# Polsador.net
KiCad netlist of a schematic drawn in EAGLE
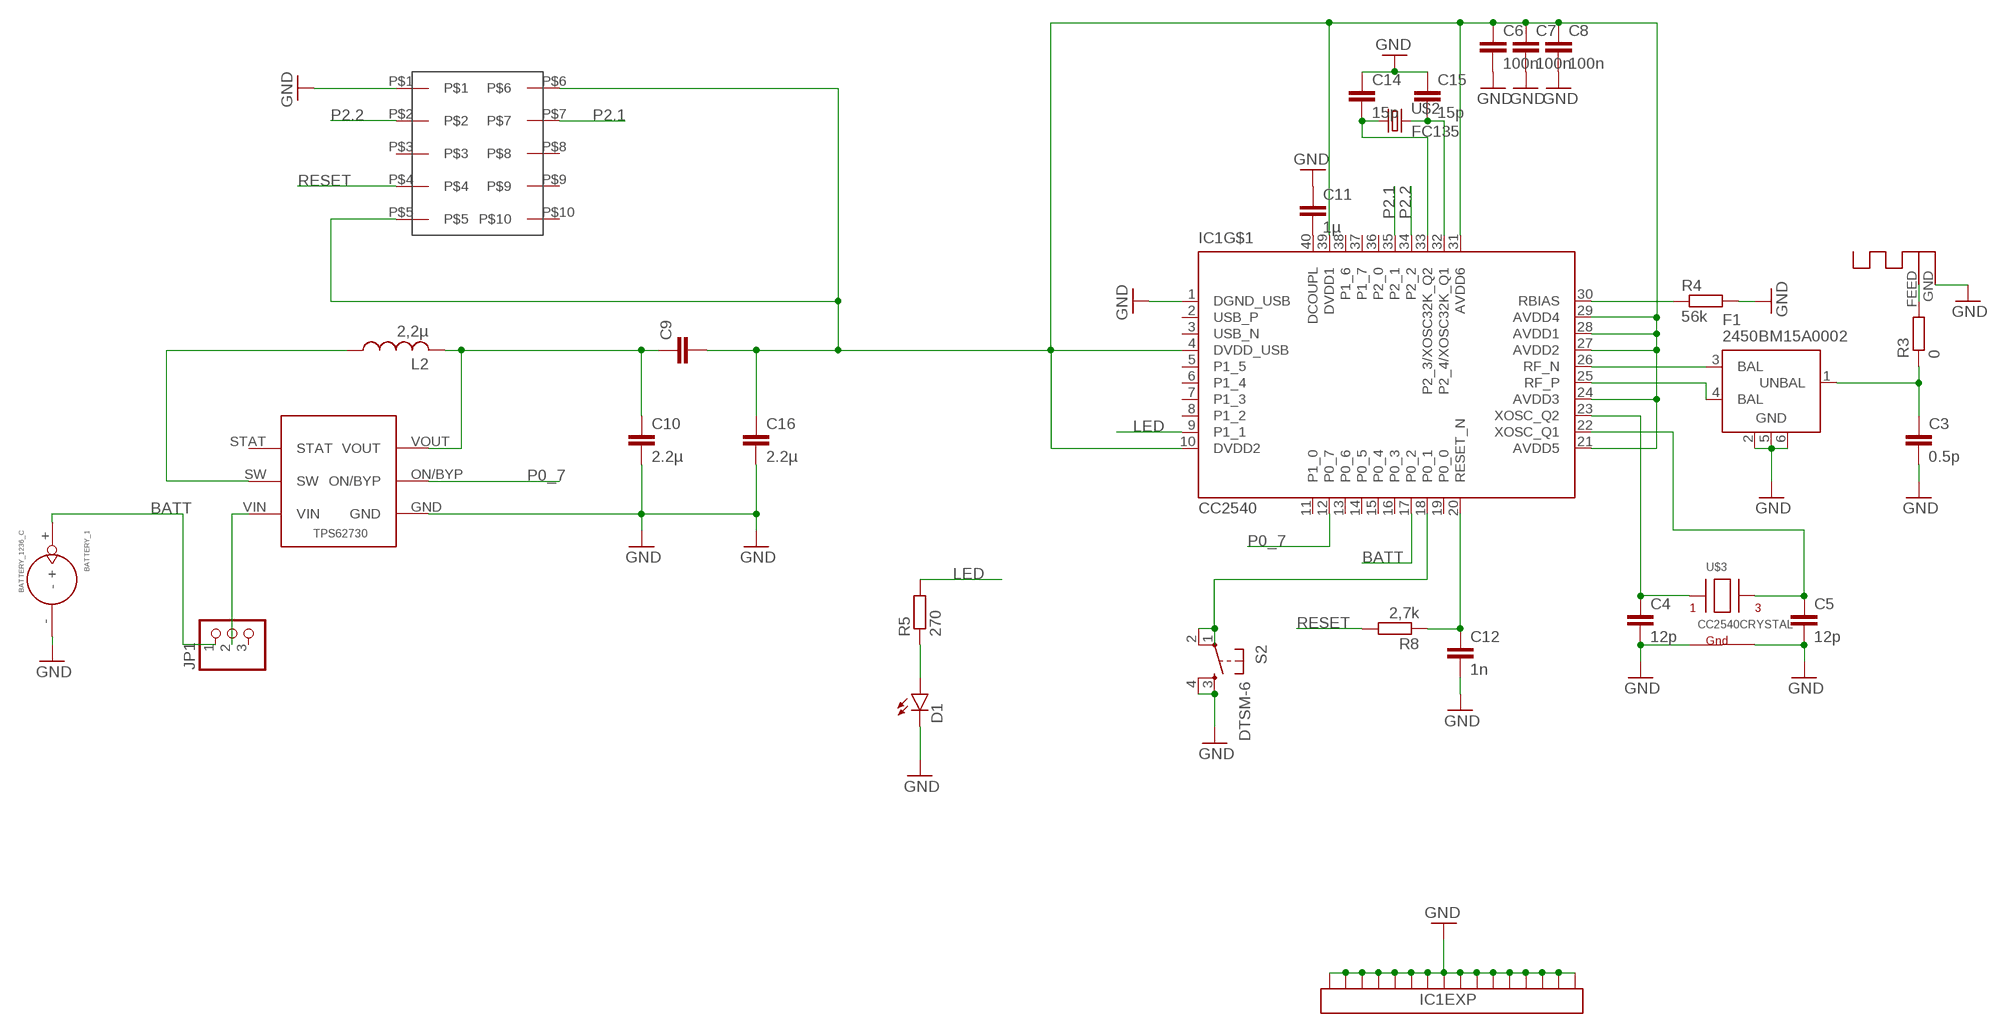
[diagram p0: schematic, sheet 1]

(export (version "E")
  (design (tool "Eeschema 10.0.6"))
  (components
    (comp (ref "ANT1")
      (value "ANTENNA")
      (footprint "eagle-import:RN-ANT")
      (libsource (lib "eagle-import") (part "ANTENNA"))
    )
    (comp (ref "BATTERY_1")
      (value "BATTERY_1236_C")
      (footprint "eagle-import:BATTERY_1236_C")
      (libsource (lib "eagle-import") (part "BATTERY_1236_C"))
    )
    (comp (ref "C3")
      (value "0.5p")
      (footprint "eagle-import:C0402K")
      (libsource (lib "eagle-import") (part "C-EUC0402K"))
    )
    (comp (ref "C4")
      (value "12p")
      (footprint "eagle-import:C0402K")
      (libsource (lib "eagle-import") (part "C-EUC0402K"))
    )
    (comp (ref "C5")
      (value "12p")
      (footprint "eagle-import:C0402K")
      (libsource (lib "eagle-import") (part "C-EUC0402K"))
    )
    (comp (ref "C6")
      (value "100n")
      (footprint "eagle-import:C0402K")
      (libsource (lib "eagle-import") (part "C-EUC0402K"))
    )
    (comp (ref "C7")
      (value "100n")
      (footprint "eagle-import:C0402K")
      (libsource (lib "eagle-import") (part "C-EUC0402K"))
    )
    (comp (ref "C8")
      (value "100n")
      (footprint "eagle-import:C0402K")
      (libsource (lib "eagle-import") (part "C-EUC0402K"))
    )
    (comp (ref "C9")
      (value "C-EUC0402")
      (footprint "eagle-import:C0402")
      (libsource (lib "eagle-import") (part "C-EUC0402"))
    )
    (comp (ref "C10")
      (value "2.2µ")
      (footprint "eagle-import:C0402K")
      (libsource (lib "eagle-import") (part "C-EUC0402K"))
    )
    (comp (ref "C11")
      (value "1µ")
      (footprint "eagle-import:C0402K")
      (libsource (lib "eagle-import") (part "C-EUC0402K"))
    )
    (comp (ref "C12")
      (value "1n")
      (footprint "eagle-import:C0402K")
      (libsource (lib "eagle-import") (part "C-EUC0402K"))
    )
    (comp (ref "C14")
      (value "15p")
      (footprint "eagle-import:C0402K")
      (libsource (lib "eagle-import") (part "C-EUC0402K"))
    )
    (comp (ref "C15")
      (value "15p")
      (footprint "eagle-import:C0402K")
      (libsource (lib "eagle-import") (part "C-EUC0402K"))
    )
    (comp (ref "C16")
      (value "2.2µ")
      (footprint "eagle-import:C0402K")
      (libsource (lib "eagle-import") (part "C-EUC0402K"))
    )
    (comp (ref "D1")
      (value "LED0603")
      (footprint "eagle-import:LED-0603")
      (libsource (lib "eagle-import") (part "LED0603"))
    )
    (comp (ref "F1")
      (value "2450BM15A0002")
      (footprint "eagle-import:2450BM15A0002")
      (libsource (lib "eagle-import") (part "2450BM15A0002"))
    )
    (comp (ref "IC1")
      (value "CC2540")
      (footprint "eagle-import:QFN40-6X6")
      (libsource (lib "eagle-import") (part "CC2540"))
    )
    (comp (ref "JP1")
      (value "PINHD-1X3")
      (footprint "eagle-import:1X03")
      (libsource (lib "eagle-import") (part "PINHD-1X3"))
    )
    (comp (ref "L2")
      (value "2,2µ")
      (footprint "eagle-import:L2012C")
      (libsource (lib "eagle-import") (part "L-USL2012C"))
    )
    (comp (ref "R3")
      (value "0")
      (footprint "eagle-import:R0402")
      (libsource (lib "eagle-import") (part "R-EU_R0402"))
    )
    (comp (ref "R4")
      (value "56k")
      (footprint "eagle-import:R0402")
      (libsource (lib "eagle-import") (part "R-EU_R0402"))
    )
    (comp (ref "R5")
      (value "270")
      (footprint "eagle-import:R0402")
      (libsource (lib "eagle-import") (part "R-EU_R0402"))
    )
    (comp (ref "R8")
      (value "2,7k")
      (footprint "eagle-import:R0402")
      (libsource (lib "eagle-import") (part "R-EU_R0402"))
    )
    (comp (ref "S2")
      (value "DTSM-6")
      (footprint "eagle-import:DTSM-6")
      (libsource (lib "eagle-import") (part "DTSM-6"))
    )
    (comp (ref "U$1")
      (value "DEBUG")
      (footprint "eagle-import:DEBUG")
      (libsource (lib "eagle-import") (part "DEBUG"))
    )
    (comp (ref "U$2")
      (value "FC135")
      (footprint "eagle-import:FC135")
      (libsource (lib "eagle-import") (part "FC135"))
    )
    (comp (ref "U$3")
      (value "CC2540CRYSTAL")
      (footprint "eagle-import:CC2540CRYSTAL")
      (libsource (lib "eagle-import") (part "CC2540CRYSTAL"))
    )
    (comp (ref "U$4")
      (value "TPS62730")
      (footprint "eagle-import:TPS62730")
      (libsource (lib "eagle-import") (part "TPS62730"))
    )
  )
  (nets
    (net (code "1") (name "/BATT") (class "Default")
      (node (ref "BATTERY_1") (pin "+") (pinfunction "+_+") (pintype "bidirectional"))
      (node (ref "IC1") (pin "17") (pinfunction "P0_2_17") (pintype "bidirectional"))
      (node (ref "JP1") (pin "1") (pinfunction "1_1") (pintype "passive"))
    )
    (net (code "2") (name "/LED") (class "Default")
      (node (ref "IC1") (pin "9") (pinfunction "P1_1_9") (pintype "bidirectional"))
      (node (ref "R5") (pin "2") (pinfunction "2_2") (pintype "passive"))
    )
    (net (code "3") (name "/P0_7") (class "Default")
      (node (ref "IC1") (pin "12") (pinfunction "P0_7_12") (pintype "bidirectional"))
      (node (ref "U$4") (pin "ON/BYP") (pinfunction "ON/BYP_ON/BYP") (pintype "bidirectional"))
    )
    (net (code "4") (name "/P2.1") (class "Default")
      (node (ref "IC1") (pin "35") (pinfunction "P2_1_35") (pintype "bidirectional"))
      (node (ref "U$1") (pin "P$7") (pinfunction "P$7_P$7") (pintype "bidirectional"))
    )
    (net (code "5") (name "/P2.2") (class "Default")
      (node (ref "IC1") (pin "34") (pinfunction "P2_2_34") (pintype "bidirectional"))
      (node (ref "U$1") (pin "P$2") (pinfunction "P$2_P$2") (pintype "bidirectional"))
    )
    (net (code "6") (name "/RESET") (class "Default")
      (node (ref "R8") (pin "2") (pinfunction "2_2") (pintype "passive"))
      (node (ref "U$1") (pin "P$4") (pinfunction "P$4_P$4") (pintype "bidirectional"))
    )
    (net (code "7") (name "GND") (class "Default")
      (node (ref "ANT1") (pin "GND") (pinfunction "GND_GND") (pintype "passive"))
      (node (ref "BATTERY_1") (pin "-") (pinfunction "-_-") (pintype "bidirectional"))
      (node (ref "C10") (pin "2") (pinfunction "2_2") (pintype "passive"))
      (node (ref "C11") (pin "1") (pinfunction "1_1") (pintype "passive"))
      (node (ref "C12") (pin "2") (pinfunction "2_2") (pintype "passive"))
      (node (ref "C14") (pin "1") (pinfunction "1_1") (pintype "passive"))
      (node (ref "C15") (pin "1") (pinfunction "1_1") (pintype "passive"))
      (node (ref "C16") (pin "2") (pinfunction "2_2") (pintype "passive"))
      (node (ref "C3") (pin "2") (pinfunction "2_2") (pintype "passive"))
      (node (ref "C4") (pin "2") (pinfunction "2_2") (pintype "passive"))
      (node (ref "C5") (pin "2") (pinfunction "2_2") (pintype "passive"))
      (node (ref "C6") (pin "2") (pinfunction "2_2") (pintype "passive"))
      (node (ref "C7") (pin "2") (pinfunction "2_2") (pintype "passive"))
      (node (ref "C8") (pin "2") (pinfunction "2_2") (pintype "passive"))
      (node (ref "D1") (pin "C") (pinfunction "C_C") (pintype "passive"))
      (node (ref "F1") (pin "2") (pinfunction "GND_2") (pintype "passive"))
      (node (ref "F1") (pin "5") (pinfunction "GND_5") (pintype "passive"))
      (node (ref "F1") (pin "6") (pinfunction "GND_6") (pintype "passive"))
      (node (ref "IC1") (pin "1") (pinfunction "DGND_USB_1") (pintype "power_in"))
      (node (ref "IC1") (pin "EXP@1") (pinfunction "EXP16_EXP@1") (pintype "input"))
      (node (ref "IC1") (pin "EXP@10") (pinfunction "EXP16_EXP@10") (pintype "input"))
      (node (ref "IC1") (pin "EXP@11") (pinfunction "EXP16_EXP@11") (pintype "input"))
      (node (ref "IC1") (pin "EXP@12") (pinfunction "EXP16_EXP@12") (pintype "input"))
      (node (ref "IC1") (pin "EXP@13") (pinfunction "EXP16_EXP@13") (pintype "input"))
      (node (ref "IC1") (pin "EXP@14") (pinfunction "EXP16_EXP@14") (pintype "input"))
      (node (ref "IC1") (pin "EXP@15") (pinfunction "EXP16_EXP@15") (pintype "input"))
      (node (ref "IC1") (pin "EXP@16") (pinfunction "EXP16_EXP@16") (pintype "input"))
      (node (ref "IC1") (pin "EXP@2") (pinfunction "EXP16_EXP@2") (pintype "input"))
      (node (ref "IC1") (pin "EXP@3") (pinfunction "EXP16_EXP@3") (pintype "input"))
      (node (ref "IC1") (pin "EXP@4") (pinfunction "EXP16_EXP@4") (pintype "input"))
      (node (ref "IC1") (pin "EXP@5") (pinfunction "EXP16_EXP@5") (pintype "input"))
      (node (ref "IC1") (pin "EXP@6") (pinfunction "EXP16_EXP@6") (pintype "input"))
      (node (ref "IC1") (pin "EXP@7") (pinfunction "EXP16_EXP@7") (pintype "input"))
      (node (ref "IC1") (pin "EXP@8") (pinfunction "EXP16_EXP@8") (pintype "input"))
      (node (ref "IC1") (pin "EXP@9") (pinfunction "EXP16_EXP@9") (pintype "input"))
      (node (ref "R4") (pin "2") (pinfunction "2_2") (pintype "passive"))
      (node (ref "S2") (pin "3") (pinfunction "3_3") (pintype "passive"))
      (node (ref "S2") (pin "4") (pinfunction "4_4") (pintype "passive"))
      (node (ref "U$1") (pin "P$1") (pinfunction "P$1_P$1") (pintype "bidirectional"))
      (node (ref "U$3") (pin "2") (pinfunction "G1_2") (pintype "power_in"))
      (node (ref "U$3") (pin "4") (pinfunction "G2_4") (pintype "power_in"))
      (node (ref "U$4") (pin "GND") (pinfunction "GND_GND") (pintype "bidirectional"))
    )
    (net (code "8") (name "Net-(ANT1-PadFEED)") (class "Default")
      (node (ref "ANT1") (pin "FEED") (pinfunction "FEED_FEED") (pintype "passive"))
      (node (ref "R3") (pin "2") (pinfunction "2_2") (pintype "passive"))
    )
    (net (code "9") (name "Net-(C10-Pad1)") (class "Default")
      (node (ref "C10") (pin "1") (pinfunction "1_1") (pintype "passive"))
      (node (ref "C9") (pin "1") (pinfunction "1_1") (pintype "passive"))
      (node (ref "L2") (pin "2") (pinfunction "2_2") (pintype "passive"))
      (node (ref "U$4") (pin "VOUT") (pinfunction "VOUT_VOUT") (pintype "bidirectional"))
    )
    (net (code "10") (name "Net-(D1-PadA)") (class "Default")
      (node (ref "D1") (pin "A") (pinfunction "A_A") (pintype "passive"))
      (node (ref "R5") (pin "1") (pinfunction "1_1") (pintype "passive"))
    )
    (net (code "11") (name "Net-(F1-UNBAL)") (class "Default")
      (node (ref "C3") (pin "1") (pinfunction "1_1") (pintype "passive"))
      (node (ref "F1") (pin "1") (pinfunction "UNBAL_1") (pintype "passive"))
      (node (ref "R3") (pin "1") (pinfunction "1_1") (pintype "passive"))
    )
    (net (code "12") (name "Net-(IC1B-AVDD1)") (class "Default")
      (node (ref "C16") (pin "1") (pinfunction "1_1") (pintype "passive"))
      (node (ref "C6") (pin "1") (pinfunction "1_1") (pintype "passive"))
      (node (ref "C7") (pin "1") (pinfunction "1_1") (pintype "passive"))
      (node (ref "C8") (pin "1") (pinfunction "1_1") (pintype "passive"))
      (node (ref "C9") (pin "2") (pinfunction "2_2") (pintype "passive"))
      (node (ref "IC1") (pin "10") (pinfunction "DVDD2_10") (pintype "power_in"))
      (node (ref "IC1") (pin "21") (pinfunction "AVDD5_21") (pintype "power_in"))
      (node (ref "IC1") (pin "24") (pinfunction "AVDD3_24") (pintype "power_in"))
      (node (ref "IC1") (pin "27") (pinfunction "AVDD2_27") (pintype "power_in"))
      (node (ref "IC1") (pin "28") (pinfunction "AVDD1_28") (pintype "power_in"))
      (node (ref "IC1") (pin "29") (pinfunction "AVDD4_29") (pintype "power_in"))
      (node (ref "IC1") (pin "31") (pinfunction "AVDD6_31") (pintype "power_in"))
      (node (ref "IC1") (pin "39") (pinfunction "DVDD1_39") (pintype "power_in"))
      (node (ref "IC1") (pin "4") (pinfunction "DVDD_USB_4") (pintype "power_in"))
      (node (ref "U$1") (pin "P$5") (pinfunction "P$5_P$5") (pintype "bidirectional"))
      (node (ref "U$1") (pin "P$6") (pinfunction "P$6_P$6") (pintype "bidirectional"))
    )
    (net (code "13") (name "Net-(IC1B-DCOUPL)") (class "Default")
      (node (ref "C11") (pin "2") (pinfunction "2_2") (pintype "passive"))
      (node (ref "IC1") (pin "40") (pinfunction "DCOUPL_40") (pintype "power_in"))
    )
    (net (code "14") (name "Net-(IC1B-P0_1)") (class "Default")
      (node (ref "IC1") (pin "18") (pinfunction "P0_1_18") (pintype "bidirectional"))
      (node (ref "S2") (pin "1") (pinfunction "1_1") (pintype "passive"))
      (node (ref "S2") (pin "2") (pinfunction "2_2") (pintype "passive"))
    )
    (net (code "15") (name "Net-(IC1B-P2_3{slash}XOSC32K_Q2)") (class "Default")
      (node (ref "C14") (pin "2") (pinfunction "2_2") (pintype "passive"))
      (node (ref "IC1") (pin "33") (pinfunction "P2_3/XOSC32K_Q2_33") (pintype "bidirectional"))
      (node (ref "U$2") (pin "1") (pinfunction "1_1") (pintype "passive"))
    )
    (net (code "16") (name "Net-(IC1B-P2_4{slash}XOSC32K_Q1)") (class "Default")
      (node (ref "C15") (pin "2") (pinfunction "2_2") (pintype "passive"))
      (node (ref "IC1") (pin "32") (pinfunction "P2_4/XOSC32K_Q1_32") (pintype "bidirectional"))
      (node (ref "U$2") (pin "2") (pinfunction "2_2") (pintype "passive"))
    )
    (net (code "17") (name "Net-(IC1B-RBIAS)") (class "Default")
      (node (ref "IC1") (pin "30") (pinfunction "RBIAS_30") (pintype "bidirectional"))
      (node (ref "R4") (pin "1") (pinfunction "1_1") (pintype "passive"))
    )
    (net (code "18") (name "Net-(IC1B-RESET_N)") (class "Default")
      (node (ref "C12") (pin "1") (pinfunction "1_1") (pintype "passive"))
      (node (ref "IC1") (pin "20") (pinfunction "RESET_N_20") (pintype "input"))
      (node (ref "R8") (pin "1") (pinfunction "1_1") (pintype "passive"))
    )
    (net (code "19") (name "Net-(IC1B-RF_N)") (class "Default")
      (node (ref "F1") (pin "3") (pinfunction "BAL_3") (pintype "passive"))
      (node (ref "IC1") (pin "26") (pinfunction "RF_N_26") (pintype "input"))
    )
    (net (code "20") (name "Net-(IC1B-RF_P)") (class "Default")
      (node (ref "F1") (pin "4") (pinfunction "BAL_4") (pintype "passive"))
      (node (ref "IC1") (pin "25") (pinfunction "RF_P_25") (pintype "input"))
    )
    (net (code "21") (name "Net-(IC1B-XOSC_Q1)") (class "Default")
      (node (ref "C5") (pin "1") (pinfunction "1_1") (pintype "passive"))
      (node (ref "IC1") (pin "22") (pinfunction "XOSC_Q1_22") (pintype "bidirectional"))
      (node (ref "U$3") (pin "3") (pinfunction "X2_3") (pintype "bidirectional"))
    )
    (net (code "22") (name "Net-(IC1B-XOSC_Q2)") (class "Default")
      (node (ref "C4") (pin "1") (pinfunction "1_1") (pintype "passive"))
      (node (ref "IC1") (pin "23") (pinfunction "XOSC_Q2_23") (pintype "bidirectional"))
      (node (ref "U$3") (pin "1") (pinfunction "X1_1") (pintype "bidirectional"))
    )
    (net (code "23") (name "Net-(JP1-Pad2)") (class "Default")
      (node (ref "JP1") (pin "2") (pinfunction "2_2") (pintype "passive"))
      (node (ref "U$4") (pin "VIN") (pinfunction "VIN_VIN") (pintype "bidirectional"))
    )
    (net (code "24") (name "Net-(L2-Pad1)") (class "Default")
      (node (ref "L2") (pin "1") (pinfunction "1_1") (pintype "passive"))
      (node (ref "U$4") (pin "SW") (pinfunction "SW_SW") (pintype "bidirectional"))
    )
    (net (code "25") (name "unconnected-(IC1B-P0_0-Pad19)") (class "Default")
      (node (ref "IC1") (pin "19") (pinfunction "P0_0_19") (pintype "bidirectional"))
    )
    (net (code "26") (name "unconnected-(IC1B-P0_3-Pad16)") (class "Default")
      (node (ref "IC1") (pin "16") (pinfunction "P0_3_16") (pintype "bidirectional"))
    )
    (net (code "27") (name "unconnected-(IC1B-P0_4-Pad15)") (class "Default")
      (node (ref "IC1") (pin "15") (pinfunction "P0_4_15") (pintype "bidirectional"))
    )
    (net (code "28") (name "unconnected-(IC1B-P0_5-Pad14)") (class "Default")
      (node (ref "IC1") (pin "14") (pinfunction "P0_5_14") (pintype "bidirectional"))
    )
    (net (code "29") (name "unconnected-(IC1B-P0_6-Pad13)") (class "Default")
      (node (ref "IC1") (pin "13") (pinfunction "P0_6_13") (pintype "bidirectional"))
    )
    (net (code "30") (name "unconnected-(IC1B-P1_0-Pad11)") (class "Default")
      (node (ref "IC1") (pin "11") (pinfunction "P1_0_11") (pintype "bidirectional"))
    )
    (net (code "31") (name "unconnected-(IC1B-P1_2-Pad8)") (class "Default")
      (node (ref "IC1") (pin "8") (pinfunction "P1_2_8") (pintype "bidirectional"))
    )
    (net (code "32") (name "unconnected-(IC1B-P1_3-Pad7)") (class "Default")
      (node (ref "IC1") (pin "7") (pinfunction "P1_3_7") (pintype "bidirectional"))
    )
    (net (code "33") (name "unconnected-(IC1B-P1_4-Pad6)") (class "Default")
      (node (ref "IC1") (pin "6") (pinfunction "P1_4_6") (pintype "bidirectional"))
    )
    (net (code "34") (name "unconnected-(IC1B-P1_5-Pad5)") (class "Default")
      (node (ref "IC1") (pin "5") (pinfunction "P1_5_5") (pintype "bidirectional"))
    )
    (net (code "35") (name "unconnected-(IC1B-P1_6-Pad38)") (class "Default")
      (node (ref "IC1") (pin "38") (pinfunction "P1_6_38") (pintype "bidirectional"))
    )
    (net (code "36") (name "unconnected-(IC1B-P1_7-Pad37)") (class "Default")
      (node (ref "IC1") (pin "37") (pinfunction "P1_7_37") (pintype "bidirectional"))
    )
    (net (code "37") (name "unconnected-(IC1B-P2_0-Pad36)") (class "Default")
      (node (ref "IC1") (pin "36") (pinfunction "P2_0_36") (pintype "bidirectional"))
    )
    (net (code "38") (name "unconnected-(IC1B-USB_N-Pad3)") (class "Default")
      (node (ref "IC1") (pin "3") (pinfunction "USB_N_3") (pintype "bidirectional"))
    )
    (net (code "39") (name "unconnected-(IC1B-USB_P-Pad2)") (class "Default")
      (node (ref "IC1") (pin "2") (pinfunction "USB_P_2") (pintype "bidirectional"))
    )
    (net (code "40") (name "unconnected-(JP1-Pad3)") (class "Default")
      (node (ref "JP1") (pin "3") (pinfunction "3_3") (pintype "passive"))
    )
    (net (code "41") (name "unconnected-(U$1-PadP$3)") (class "Default")
      (node (ref "U$1") (pin "P$3") (pinfunction "P$3_P$3") (pintype "bidirectional"))
    )
    (net (code "42") (name "unconnected-(U$1-PadP$8)") (class "Default")
      (node (ref "U$1") (pin "P$8") (pinfunction "P$8_P$8") (pintype "bidirectional"))
    )
    (net (code "43") (name "unconnected-(U$1-PadP$9)") (class "Default")
      (node (ref "U$1") (pin "P$9") (pinfunction "P$9_P$9") (pintype "bidirectional"))
    )
    (net (code "44") (name "unconnected-(U$1-PadP$10)") (class "Default")
      (node (ref "U$1") (pin "P$10") (pinfunction "P$10_P$10") (pintype "bidirectional"))
    )
    (net (code "45") (name "unconnected-(U$4-PadSTAT)") (class "Default")
      (node (ref "U$4") (pin "STAT") (pinfunction "STAT_STAT") (pintype "bidirectional"))
    )
  )
)
